# RemoteR1_0.net
KiCad netlist of a schematic drawn in EAGLE
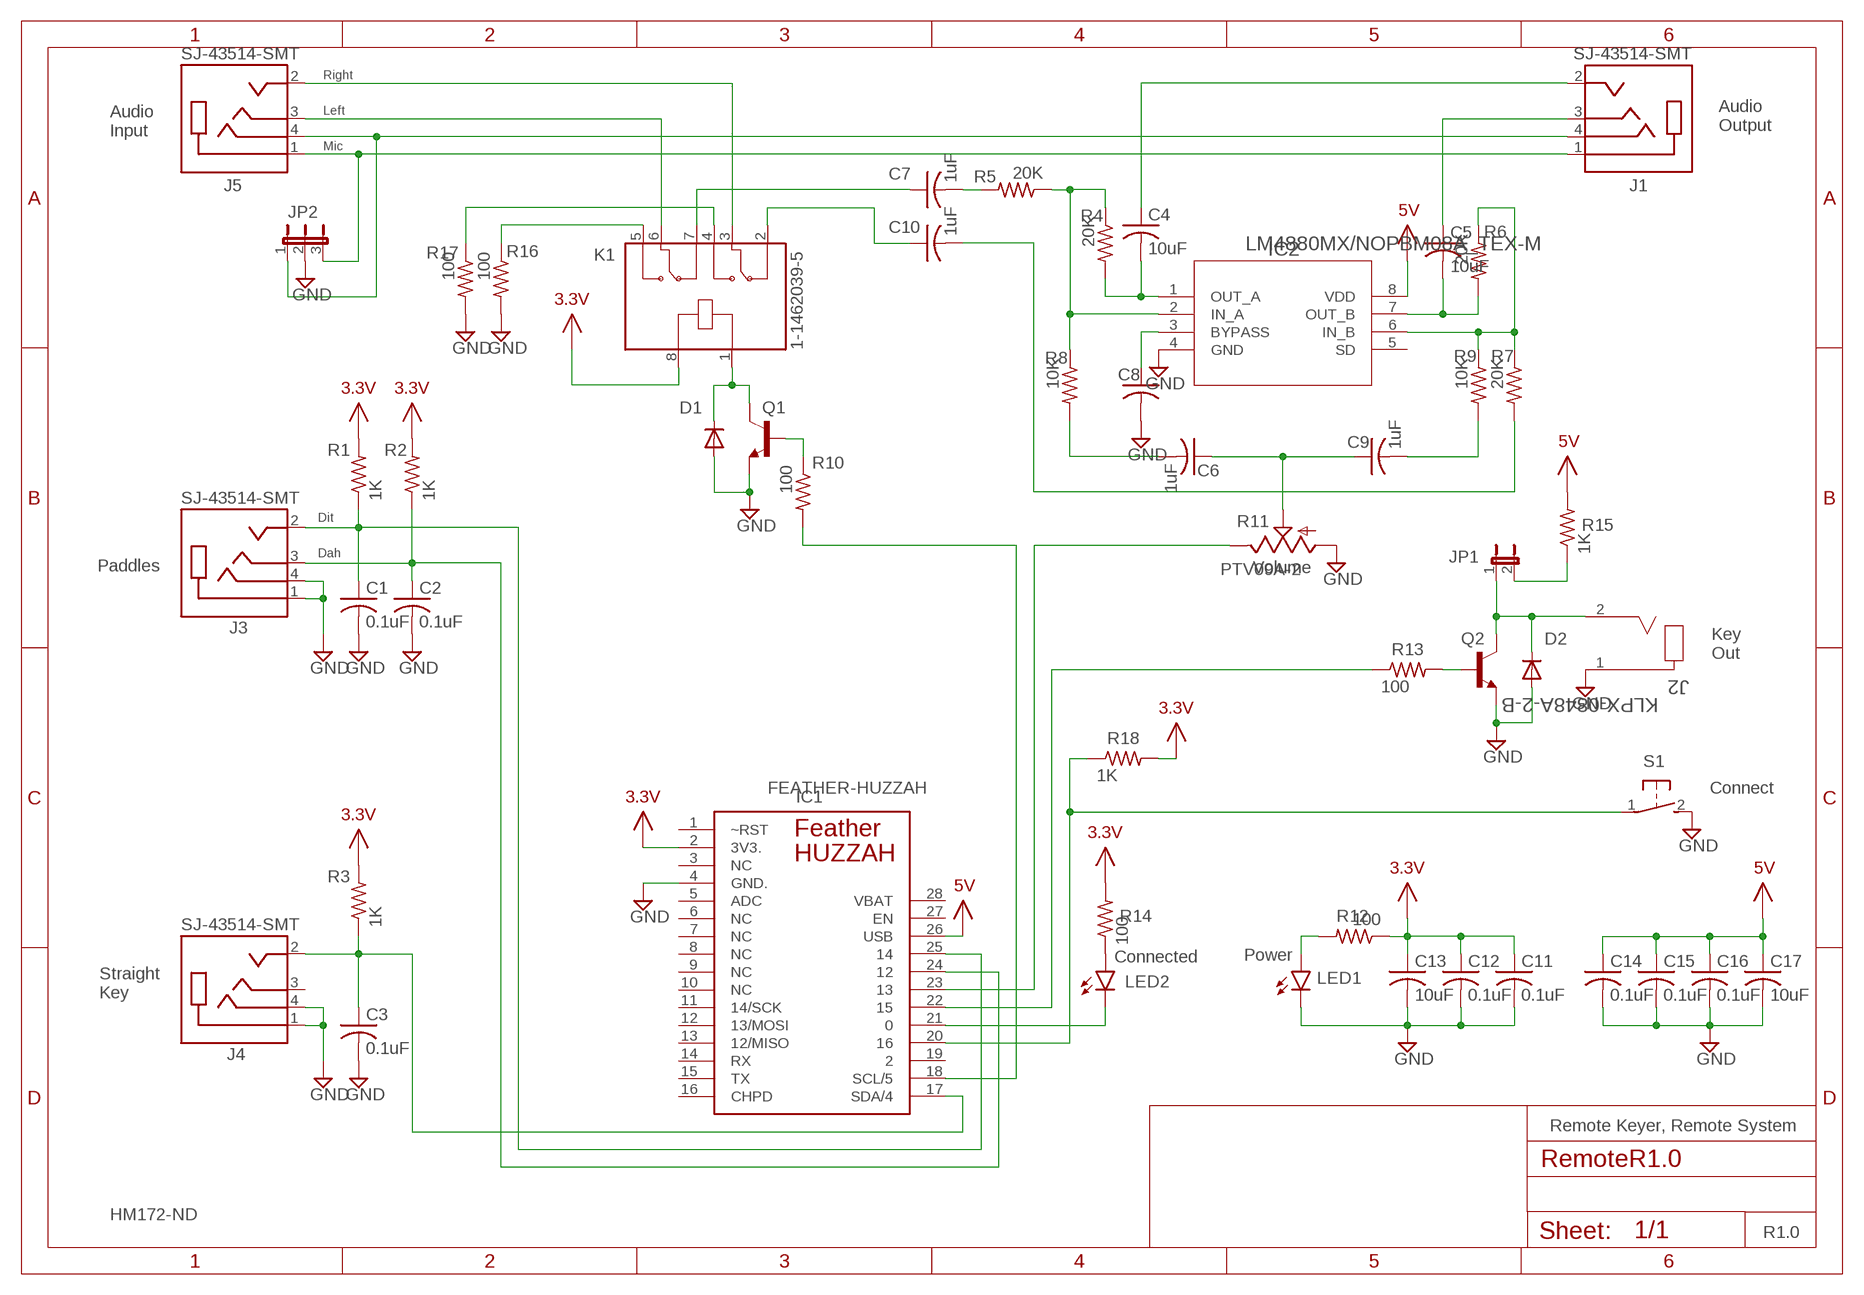
[diagram p0: schematic, sheet 1]

(export (version "E")
  (design (tool "Eeschema 10.0.6"))
  (components
    (comp (ref "C1")
      (value "0.1uF")
      (footprint "eagle-import:C0805")
      (libsource (lib "eagle-import") (part "C-USC0805"))
    )
    (comp (ref "C2")
      (value "0.1uF")
      (footprint "eagle-import:C0805")
      (libsource (lib "eagle-import") (part "C-USC0805"))
    )
    (comp (ref "C3")
      (value "0.1uF")
      (footprint "eagle-import:C0805")
      (libsource (lib "eagle-import") (part "C-USC0805"))
    )
    (comp (ref "C4")
      (value "10uF")
      (footprint "eagle-import:C1206")
      (libsource (lib "eagle-import") (part "C-USC1206"))
    )
    (comp (ref "C5")
      (value "10uF")
      (footprint "eagle-import:C1206")
      (libsource (lib "eagle-import") (part "C-USC1206"))
    )
    (comp (ref "C6")
      (value "1uF")
      (footprint "eagle-import:C0805")
      (libsource (lib "eagle-import") (part "C-USC0805"))
    )
    (comp (ref "C7")
      (value "1uF")
      (footprint "eagle-import:C0805")
      (libsource (lib "eagle-import") (part "C-USC0805"))
    )
    (comp (ref "C8")
      (value "C-USC0805")
      (footprint "eagle-import:C0805")
      (libsource (lib "eagle-import") (part "C-USC0805"))
    )
    (comp (ref "C9")
      (value "1uF")
      (footprint "eagle-import:C0805")
      (libsource (lib "eagle-import") (part "C-USC0805"))
    )
    (comp (ref "C10")
      (value "1uF")
      (footprint "eagle-import:C0805")
      (libsource (lib "eagle-import") (part "C-USC0805"))
    )
    (comp (ref "C11")
      (value "0.1uF")
      (footprint "eagle-import:C0805")
      (libsource (lib "eagle-import") (part "C-USC0805"))
    )
    (comp (ref "C12")
      (value "0.1uF")
      (footprint "eagle-import:C0805")
      (libsource (lib "eagle-import") (part "C-USC0805"))
    )
    (comp (ref "C13")
      (value "10uF")
      (footprint "eagle-import:C0805")
      (libsource (lib "eagle-import") (part "C-USC0805"))
    )
    (comp (ref "C14")
      (value "0.1uF")
      (footprint "eagle-import:C0805")
      (libsource (lib "eagle-import") (part "C-USC0805"))
    )
    (comp (ref "C15")
      (value "0.1uF")
      (footprint "eagle-import:C0805")
      (libsource (lib "eagle-import") (part "C-USC0805"))
    )
    (comp (ref "C16")
      (value "0.1uF")
      (footprint "eagle-import:C0805")
      (libsource (lib "eagle-import") (part "C-USC0805"))
    )
    (comp (ref "C17")
      (value "10uF")
      (footprint "eagle-import:C0805")
      (libsource (lib "eagle-import") (part "C-USC0805"))
    )
    (comp (ref "D1")
      (value "DIODE-SOD323-R")
      (footprint "eagle-import:SOD323-R")
      (libsource (lib "eagle-import") (part "DIODE-SOD323-R"))
    )
    (comp (ref "D2")
      (value "DIODE-SOD323-R")
      (footprint "eagle-import:SOD323-R")
      (libsource (lib "eagle-import") (part "DIODE-SOD323-R"))
    )
    (comp (ref "IC1")
      (value "FEATHER-HUZZAH")
      (footprint "eagle-import:FEATHER-HUZZAH")
      (libsource (lib "eagle-import") (part "FEATHER-HUZZAH"))
    )
    (comp (ref "IC2")
      (value "LM4880MX/NOPBM08A_TEX-M")
      (footprint "eagle-import:M08A_TEX-M")
      (fields
        (field (name "MANUFACTURER_PART_NUMBER") "LM4880MX/NOPB")
        (field (name "COPYRIGHT") "Copyright (C) 2021 Ultra Librarian. All rights reserved.")
      )
      (libsource (lib "eagle-import") (part "LM4880MX/NOPBM08A_TEX-M"))
    )
    (comp (ref "J1")
      (value "SJ-43514-SMT")
      (footprint "eagle-import:CUI_SJ-43514-SMT")
      (fields (field (name "MF") "CUI Devices") (field (name "MP") "SJ-43514-SMT-TR"))
      (libsource (lib "eagle-import") (part "SJ-43514-SMT"))
    )
    (comp (ref "J2")
      (value "KLPX-0848A-2-B")
      (footprint "eagle-import:KLPX-0848A-2-B_KYC")
      (fields (field (name "COPYRIGHT") "Copyright (C) 2021 Ultra Librarian. All rights reserved."))
      (libsource (lib "eagle-import") (part "KLPX-0848A-2-B"))
    )
    (comp (ref "J3")
      (value "SJ-43514-SMT")
      (footprint "eagle-import:CUI_SJ-43514-SMT")
      (fields (field (name "MF") "CUI Devices") (field (name "MP") "SJ-43514-SMT-TR"))
      (libsource (lib "eagle-import") (part "SJ-43514-SMT"))
    )
    (comp (ref "J4")
      (value "SJ-43514-SMT")
      (footprint "eagle-import:CUI_SJ-43514-SMT")
      (fields (field (name "MF") "CUI Devices") (field (name "MP") "SJ-43514-SMT-TR"))
      (libsource (lib "eagle-import") (part "SJ-43514-SMT"))
    )
    (comp (ref "J5")
      (value "SJ-43514-SMT")
      (footprint "eagle-import:CUI_SJ-43514-SMT")
      (fields (field (name "MF") "CUI Devices") (field (name "MP") "SJ-43514-SMT-TR"))
      (libsource (lib "eagle-import") (part "SJ-43514-SMT"))
    )
    (comp (ref "JP1")
      (value "JP1E")
      (footprint "eagle-import:JP1")
      (libsource (lib "eagle-import") (part "JP1E"))
    )
    (comp (ref "JP2")
      (value "JP2E")
      (footprint "eagle-import:JP2")
      (libsource (lib "eagle-import") (part "JP2E"))
    )
    (comp (ref "K1")
      (value "1-1462039-5")
      (footprint "eagle-import:RELAY_1-1462039-5")
      (fields (field (name "DIGI-KEY_PART_NUMBER") "PB1167-ND") (field (name "MF") "TE Connectivity"))
      (libsource (lib "eagle-import") (part "1-1462039-5"))
    )
    (comp (ref "LED1")
      (value "LED5MM")
      (footprint "eagle-import:LED5MM")
      (libsource (lib "eagle-import") (part "LED5MM"))
    )
    (comp (ref "LED2")
      (value "LED5MM")
      (footprint "eagle-import:LED5MM")
      (libsource (lib "eagle-import") (part "LED5MM"))
    )
    (comp (ref "Q1")
      (value "MMBT2369LT1-NPN-SOT23-BEC")
      (footprint "eagle-import:SOT23-BEC")
      (libsource (lib "eagle-import") (part "-NPN-SOT23-BECMMBT2369LT1"))
    )
    (comp (ref "Q2")
      (value "MMBT2369LT1-NPN-SOT23-BEC")
      (footprint "eagle-import:SOT23-BEC")
      (libsource (lib "eagle-import") (part "-NPN-SOT23-BECMMBT2369LT1"))
    )
    (comp (ref "R1")
      (value "1K")
      (footprint "eagle-import:R0805")
      (libsource (lib "eagle-import") (part "R-US_R0805"))
    )
    (comp (ref "R2")
      (value "1K")
      (footprint "eagle-import:R0805")
      (libsource (lib "eagle-import") (part "R-US_R0805"))
    )
    (comp (ref "R3")
      (value "1K")
      (footprint "eagle-import:R0805")
      (libsource (lib "eagle-import") (part "R-US_R0805"))
    )
    (comp (ref "R4")
      (value "20K")
      (footprint "eagle-import:R0805")
      (libsource (lib "eagle-import") (part "R-US_R0805"))
    )
    (comp (ref "R5")
      (value "20K")
      (footprint "eagle-import:R0805")
      (libsource (lib "eagle-import") (part "R-US_R0805"))
    )
    (comp (ref "R6")
      (value "20K")
      (footprint "eagle-import:R0805")
      (libsource (lib "eagle-import") (part "R-US_R0805"))
    )
    (comp (ref "R7")
      (value "20K")
      (footprint "eagle-import:R0805")
      (libsource (lib "eagle-import") (part "R-US_R0805"))
    )
    (comp (ref "R8")
      (value "10K")
      (footprint "eagle-import:R0805")
      (libsource (lib "eagle-import") (part "R-US_R0805"))
    )
    (comp (ref "R9")
      (value "10K")
      (footprint "eagle-import:R0805")
      (libsource (lib "eagle-import") (part "R-US_R0805"))
    )
    (comp (ref "R10")
      (value "100")
      (footprint "eagle-import:R0805")
      (libsource (lib "eagle-import") (part "R-US_R0805"))
    )
    (comp (ref "R11")
      (value "PTV09A-2")
      (footprint "eagle-import:PTV09A-2")
      (libsource (lib "eagle-import") (part "PTV09A-2"))
    )
    (comp (ref "R12")
      (value "100")
      (footprint "eagle-import:R0805")
      (libsource (lib "eagle-import") (part "R-US_R0805"))
    )
    (comp (ref "R13")
      (value "100")
      (footprint "eagle-import:R0805")
      (libsource (lib "eagle-import") (part "R-US_R0805"))
    )
    (comp (ref "R14")
      (value "100")
      (footprint "eagle-import:R0805")
      (libsource (lib "eagle-import") (part "R-US_R0805"))
    )
    (comp (ref "R15")
      (value "1K")
      (footprint "eagle-import:R0805")
      (libsource (lib "eagle-import") (part "R-US_R0805"))
    )
    (comp (ref "R16")
      (value "100")
      (footprint "eagle-import:R1206")
      (libsource (lib "eagle-import") (part "R-US_R1206"))
    )
    (comp (ref "R17")
      (value "100")
      (footprint "eagle-import:R1206")
      (libsource (lib "eagle-import") (part "R-US_R1206"))
    )
    (comp (ref "R18")
      (value "1K")
      (footprint "eagle-import:R0805")
      (libsource (lib "eagle-import") (part "R-US_R0805"))
    )
    (comp (ref "S1")
      (value "31-XX")
      (footprint "eagle-import:B3F-31XX")
      (fields (field (name "MPN") "B3F-3100"))
      (libsource (lib "eagle-import") (part "31-XX"))
    )
  )
  (nets
    (net (code "1") (name "/CHPD") (class "Default")
      (node (ref "IC1") (pin "16") (pinfunction "CHPD_16") (pintype "power_in"))
    )
    (net (code "2") (name "/VBAT") (class "Default")
      (node (ref "IC1") (pin "28") (pinfunction "VBAT_28") (pintype "power_in"))
    )
    (net (code "3") (name "3.3V") (class "Default")
      (node (ref "C11") (pin "1") (pinfunction "1_1") (pintype "passive"))
      (node (ref "C12") (pin "1") (pinfunction "1_1") (pintype "passive"))
      (node (ref "C13") (pin "1") (pinfunction "1_1") (pintype "passive"))
      (node (ref "IC1") (pin "2") (pinfunction "3V3._2") (pintype "power_in"))
      (node (ref "K1") (pin "8") (pinfunction "8_8") (pintype "passive"))
      (node (ref "R1") (pin "2") (pinfunction "2_2") (pintype "passive"))
      (node (ref "R12") (pin "1") (pinfunction "1_1") (pintype "passive"))
      (node (ref "R14") (pin "2") (pinfunction "2_2") (pintype "passive"))
      (node (ref "R18") (pin "2") (pinfunction "2_2") (pintype "passive"))
      (node (ref "R2") (pin "2") (pinfunction "2_2") (pintype "passive"))
      (node (ref "R3") (pin "2") (pinfunction "2_2") (pintype "passive"))
    )
    (net (code "4") (name "5V") (class "Default")
      (node (ref "C14") (pin "1") (pinfunction "1_1") (pintype "passive"))
      (node (ref "C15") (pin "1") (pinfunction "1_1") (pintype "passive"))
      (node (ref "C16") (pin "1") (pinfunction "1_1") (pintype "passive"))
      (node (ref "C17") (pin "1") (pinfunction "1_1") (pintype "passive"))
      (node (ref "IC1") (pin "26") (pinfunction "USB_26") (pintype "power_in"))
      (node (ref "IC2") (pin "8") (pinfunction "VDD_8") (pintype "power_in"))
      (node (ref "R15") (pin "2") (pinfunction "2_2") (pintype "passive"))
    )
    (net (code "5") (name "GND") (class "Default")
      (node (ref "C1") (pin "2") (pinfunction "2_2") (pintype "passive"))
      (node (ref "C11") (pin "2") (pinfunction "2_2") (pintype "passive"))
      (node (ref "C12") (pin "2") (pinfunction "2_2") (pintype "passive"))
      (node (ref "C13") (pin "2") (pinfunction "2_2") (pintype "passive"))
      (node (ref "C14") (pin "2") (pinfunction "2_2") (pintype "passive"))
      (node (ref "C15") (pin "2") (pinfunction "2_2") (pintype "passive"))
      (node (ref "C16") (pin "2") (pinfunction "2_2") (pintype "passive"))
      (node (ref "C17") (pin "2") (pinfunction "2_2") (pintype "passive"))
      (node (ref "C2") (pin "2") (pinfunction "2_2") (pintype "passive"))
      (node (ref "C3") (pin "2") (pinfunction "2_2") (pintype "passive"))
      (node (ref "C8") (pin "2") (pinfunction "2_2") (pintype "passive"))
      (node (ref "D1") (pin "A") (pinfunction "A_A") (pintype "passive"))
      (node (ref "D2") (pin "A") (pinfunction "A_A") (pintype "passive"))
      (node (ref "IC1") (pin "4") (pinfunction "GND._4") (pintype "power_in"))
      (node (ref "IC2") (pin "4") (pinfunction "GND_4") (pintype "power_in"))
      (node (ref "J2") (pin "1") (pinfunction "1_1") (pintype "passive"))
      (node (ref "J3") (pin "1") (pinfunction "SLEEVE_1") (pintype "passive"))
      (node (ref "J3") (pin "4") (pinfunction "RING2_4") (pintype "passive"))
      (node (ref "J4") (pin "1") (pinfunction "SLEEVE_1") (pintype "passive"))
      (node (ref "J4") (pin "4") (pinfunction "RING2_4") (pintype "passive"))
      (node (ref "JP2") (pin "2") (pinfunction "2_2") (pintype "passive"))
      (node (ref "LED1") (pin "K") (pinfunction "C_K") (pintype "passive"))
      (node (ref "Q1") (pin "E") (pinfunction "E_E") (pintype "passive"))
      (node (ref "Q2") (pin "E") (pinfunction "E_E") (pintype "passive"))
      (node (ref "R11") (pin "1") (pinfunction "A_1") (pintype "passive"))
      (node (ref "R16") (pin "2") (pinfunction "2_2") (pintype "passive"))
      (node (ref "R17") (pin "2") (pinfunction "2_2") (pintype "passive"))
      (node (ref "S1") (pin "2") (pinfunction "S_2") (pintype "passive"))
    )
    (net (code "6") (name "Net-(C6-Pad2)") (class "Default")
      (node (ref "C6") (pin "2") (pinfunction "2_2") (pintype "passive"))
      (node (ref "R8") (pin "2") (pinfunction "2_2") (pintype "passive"))
    )
    (net (code "7") (name "Net-(C7-Pad1)") (class "Default")
      (node (ref "C7") (pin "1") (pinfunction "1_1") (pintype "passive"))
      (node (ref "K1") (pin "7") (pinfunction "7_7") (pintype "passive"))
    )
    (net (code "8") (name "Net-(C7-Pad2)") (class "Default")
      (node (ref "C7") (pin "2") (pinfunction "2_2") (pintype "passive"))
      (node (ref "R5") (pin "2") (pinfunction "2_2") (pintype "passive"))
    )
    (net (code "9") (name "Net-(C9-Pad2)") (class "Default")
      (node (ref "C9") (pin "2") (pinfunction "2_2") (pintype "passive"))
      (node (ref "R9") (pin "2") (pinfunction "2_2") (pintype "passive"))
    )
    (net (code "10") (name "Net-(C10-Pad1)") (class "Default")
      (node (ref "C10") (pin "1") (pinfunction "1_1") (pintype "passive"))
      (node (ref "K1") (pin "2") (pinfunction "2_2") (pintype "passive"))
    )
    (net (code "11") (name "Net-(C10-Pad2)") (class "Default")
      (node (ref "C10") (pin "2") (pinfunction "2_2") (pintype "passive"))
      (node (ref "R7") (pin "2") (pinfunction "2_2") (pintype "passive"))
    )
    (net (code "12") (name "Net-(D1-PadC)") (class "Default")
      (node (ref "D1") (pin "C") (pinfunction "C_C") (pintype "passive"))
      (node (ref "K1") (pin "1") (pinfunction "1_1") (pintype "passive"))
      (node (ref "Q1") (pin "C") (pinfunction "C_C") (pintype "passive"))
    )
    (net (code "13") (name "Net-(D2-PadC)") (class "Default")
      (node (ref "D2") (pin "C") (pinfunction "C_C") (pintype "passive"))
      (node (ref "J2") (pin "2") (pinfunction "2_2") (pintype "passive"))
      (node (ref "JP1") (pin "1") (pinfunction "1_1") (pintype "passive"))
      (node (ref "Q2") (pin "C") (pinfunction "C_C") (pintype "passive"))
    )
    (net (code "14") (name "Net-(IC1-0)") (class "Default")
      (node (ref "IC1") (pin "21") (pinfunction "0_21") (pintype "bidirectional"))
      (node (ref "LED2") (pin "K") (pinfunction "C_K") (pintype "passive"))
    )
    (net (code "15") (name "Net-(IC1-12)") (class "Default")
      (node (ref "C2") (pin "1") (pinfunction "1_1") (pintype "passive"))
      (node (ref "IC1") (pin "24") (pinfunction "12_24") (pintype "bidirectional"))
      (node (ref "J3") (pin "3") (pinfunction "RING1_3") (pintype "passive"))
      (node (ref "R2") (pin "1") (pinfunction "1_1") (pintype "passive"))
    )
    (net (code "16") (name "Net-(IC1-13)") (class "Default")
      (node (ref "IC1") (pin "23") (pinfunction "13_23") (pintype "bidirectional"))
      (node (ref "R11") (pin "3") (pinfunction "E_3") (pintype "passive"))
    )
    (net (code "17") (name "Net-(IC1-14)") (class "Default")
      (node (ref "C1") (pin "1") (pinfunction "1_1") (pintype "passive"))
      (node (ref "IC1") (pin "25") (pinfunction "14_25") (pintype "bidirectional"))
      (node (ref "J3") (pin "2") (pinfunction "TIP_2") (pintype "passive"))
      (node (ref "R1") (pin "1") (pinfunction "1_1") (pintype "passive"))
    )
    (net (code "18") (name "Net-(IC1-15)") (class "Default")
      (node (ref "IC1") (pin "22") (pinfunction "15_22") (pintype "bidirectional"))
      (node (ref "R13") (pin "1") (pinfunction "1_1") (pintype "passive"))
    )
    (net (code "19") (name "Net-(IC1-16)") (class "Default")
      (node (ref "IC1") (pin "20") (pinfunction "16_20") (pintype "bidirectional"))
      (node (ref "R18") (pin "1") (pinfunction "1_1") (pintype "passive"))
      (node (ref "S1") (pin "1") (pinfunction "P_1") (pintype "passive"))
    )
    (net (code "20") (name "Net-(IC1-SCL{slash}5)") (class "Default")
      (node (ref "IC1") (pin "18") (pinfunction "SCL/5_18") (pintype "bidirectional"))
      (node (ref "R10") (pin "2") (pinfunction "2_2") (pintype "passive"))
    )
    (net (code "21") (name "Net-(IC1-SDA{slash}4)") (class "Default")
      (node (ref "C3") (pin "1") (pinfunction "1_1") (pintype "passive"))
      (node (ref "IC1") (pin "17") (pinfunction "SDA/4_17") (pintype "bidirectional"))
      (node (ref "J4") (pin "2") (pinfunction "TIP_2") (pintype "passive"))
      (node (ref "R3") (pin "1") (pinfunction "1_1") (pintype "passive"))
    )
    (net (code "22") (name "Net-(IC2-BYPASS)") (class "Default")
      (node (ref "C8") (pin "1") (pinfunction "1_1") (pintype "passive"))
      (node (ref "IC2") (pin "3") (pinfunction "BYPASS_3") (pintype "passive"))
    )
    (net (code "23") (name "Net-(IC2-IN_A)") (class "Default")
      (node (ref "IC2") (pin "2") (pinfunction "IN_A_2") (pintype "input"))
      (node (ref "R4") (pin "1") (pinfunction "1_1") (pintype "passive"))
      (node (ref "R5") (pin "1") (pinfunction "1_1") (pintype "passive"))
      (node (ref "R8") (pin "1") (pinfunction "1_1") (pintype "passive"))
    )
    (net (code "24") (name "Net-(IC2-IN_B)") (class "Default")
      (node (ref "IC2") (pin "6") (pinfunction "IN_B_6") (pintype "input"))
      (node (ref "R6") (pin "1") (pinfunction "1_1") (pintype "passive"))
      (node (ref "R7") (pin "1") (pinfunction "1_1") (pintype "passive"))
      (node (ref "R9") (pin "1") (pinfunction "1_1") (pintype "passive"))
    )
    (net (code "25") (name "Net-(IC2-OUT_A)") (class "Default")
      (node (ref "C4") (pin "2") (pinfunction "2_2") (pintype "passive"))
      (node (ref "IC2") (pin "1") (pinfunction "OUT_A_1") (pintype "output"))
      (node (ref "R4") (pin "2") (pinfunction "2_2") (pintype "passive"))
    )
    (net (code "26") (name "Net-(IC2-OUT_B)") (class "Default")
      (node (ref "C5") (pin "2") (pinfunction "2_2") (pintype "passive"))
      (node (ref "IC2") (pin "7") (pinfunction "OUT_B_7") (pintype "output"))
      (node (ref "R6") (pin "2") (pinfunction "2_2") (pintype "passive"))
    )
    (net (code "27") (name "Net-(J1-RING1)") (class "Default")
      (node (ref "C5") (pin "1") (pinfunction "1_1") (pintype "passive"))
      (node (ref "J1") (pin "3") (pinfunction "RING1_3") (pintype "passive"))
    )
    (net (code "28") (name "Net-(J1-RING2)") (class "Default")
      (node (ref "J1") (pin "4") (pinfunction "RING2_4") (pintype "passive"))
      (node (ref "J5") (pin "4") (pinfunction "RING2_4") (pintype "passive"))
      (node (ref "JP2") (pin "1") (pinfunction "1_1") (pintype "passive"))
    )
    (net (code "29") (name "Net-(J1-SLEEVE)") (class "Default")
      (node (ref "J1") (pin "1") (pinfunction "SLEEVE_1") (pintype "passive"))
      (node (ref "J5") (pin "1") (pinfunction "SLEEVE_1") (pintype "passive"))
      (node (ref "JP2") (pin "3") (pinfunction "3_3") (pintype "passive"))
    )
    (net (code "30") (name "Net-(J1-TIP)") (class "Default")
      (node (ref "C4") (pin "1") (pinfunction "1_1") (pintype "passive"))
      (node (ref "J1") (pin "2") (pinfunction "TIP_2") (pintype "passive"))
    )
    (net (code "31") (name "Net-(J5-RING1)") (class "Default")
      (node (ref "J5") (pin "3") (pinfunction "RING1_3") (pintype "passive"))
      (node (ref "K1") (pin "6") (pinfunction "6_6") (pintype "passive"))
    )
    (net (code "32") (name "Net-(J5-TIP)") (class "Default")
      (node (ref "J5") (pin "2") (pinfunction "TIP_2") (pintype "passive"))
      (node (ref "K1") (pin "3") (pinfunction "3_3") (pintype "passive"))
    )
    (net (code "33") (name "Net-(JP1-Pad2)") (class "Default")
      (node (ref "JP1") (pin "2") (pinfunction "2_2") (pintype "passive"))
      (node (ref "R15") (pin "1") (pinfunction "1_1") (pintype "passive"))
    )
    (net (code "34") (name "Net-(K1-Pad4)") (class "Default")
      (node (ref "K1") (pin "4") (pinfunction "4_4") (pintype "passive"))
      (node (ref "R17") (pin "1") (pinfunction "1_1") (pintype "passive"))
    )
    (net (code "35") (name "Net-(K1-Pad5)") (class "Default")
      (node (ref "K1") (pin "5") (pinfunction "5_5") (pintype "passive"))
      (node (ref "R16") (pin "1") (pinfunction "1_1") (pintype "passive"))
    )
    (net (code "36") (name "Net-(LED1-PadA)") (class "Default")
      (node (ref "LED1") (pin "A") (pinfunction "A_A") (pintype "passive"))
      (node (ref "R12") (pin "2") (pinfunction "2_2") (pintype "passive"))
    )
    (net (code "37") (name "Net-(LED2-PadA)") (class "Default")
      (node (ref "LED2") (pin "A") (pinfunction "A_A") (pintype "passive"))
      (node (ref "R14") (pin "1") (pinfunction "1_1") (pintype "passive"))
    )
    (net (code "38") (name "Net-(Q1-PadB)") (class "Default")
      (node (ref "Q1") (pin "B") (pinfunction "B_B") (pintype "passive"))
      (node (ref "R10") (pin "1") (pinfunction "1_1") (pintype "passive"))
    )
    (net (code "39") (name "Net-(Q2-PadB)") (class "Default")
      (node (ref "Q2") (pin "B") (pinfunction "B_B") (pintype "passive"))
      (node (ref "R13") (pin "2") (pinfunction "2_2") (pintype "passive"))
    )
    (net (code "40") (name "Net-(R11-S)") (class "Default")
      (node (ref "C6") (pin "1") (pinfunction "1_1") (pintype "passive"))
      (node (ref "C9") (pin "1") (pinfunction "1_1") (pintype "passive"))
      (node (ref "R11") (pin "2") (pinfunction "S_2") (pintype "passive"))
    )
    (net (code "41") (name "unconnected-(IC1-2-Pad19)") (class "Default")
      (node (ref "IC1") (pin "19") (pinfunction "2_19") (pintype "bidirectional"))
    )
    (net (code "42") (name "unconnected-(IC1-12{slash}MISO-Pad13)") (class "Default")
      (node (ref "IC1") (pin "13") (pinfunction "12/MISO_13") (pintype "bidirectional"))
    )
    (net (code "43") (name "unconnected-(IC1-13{slash}MOSI-Pad12)") (class "Default")
      (node (ref "IC1") (pin "12") (pinfunction "13/MOSI_12") (pintype "bidirectional"))
    )
    (net (code "44") (name "unconnected-(IC1-14{slash}SCK-Pad11)") (class "Default")
      (node (ref "IC1") (pin "11") (pinfunction "14/SCK_11") (pintype "bidirectional"))
    )
    (net (code "45") (name "unconnected-(IC1-ADC-Pad5)") (class "Default")
      (node (ref "IC1") (pin "5") (pinfunction "ADC_5") (pintype "bidirectional"))
    )
    (net (code "46") (name "unconnected-(IC1-EN-Pad27)") (class "Default")
      (node (ref "IC1") (pin "27") (pinfunction "EN_27") (pintype "input"))
    )
    (net (code "47") (name "unconnected-(IC1-NC-Pad3)") (class "Default")
      (node (ref "IC1") (pin "3") (pinfunction "NC_3") (pintype "input"))
    )
    (net (code "48") (name "unconnected-(IC1-NC-Pad6)") (class "Default")
      (node (ref "IC1") (pin "6") (pinfunction "NC_6") (pintype "bidirectional"))
    )
    (net (code "49") (name "unconnected-(IC1-NC-Pad7)") (class "Default")
      (node (ref "IC1") (pin "7") (pinfunction "NC_7") (pintype "bidirectional"))
    )
    (net (code "50") (name "unconnected-(IC1-NC-Pad8)") (class "Default")
      (node (ref "IC1") (pin "8") (pinfunction "NC_8") (pintype "bidirectional"))
    )
    (net (code "51") (name "unconnected-(IC1-NC-Pad9)") (class "Default")
      (node (ref "IC1") (pin "9") (pinfunction "NC_9") (pintype "bidirectional"))
    )
    (net (code "52") (name "unconnected-(IC1-NC-Pad10)") (class "Default")
      (node (ref "IC1") (pin "10") (pinfunction "NC_10") (pintype "bidirectional"))
    )
    (net (code "53") (name "unconnected-(IC1-RX-Pad14)") (class "Default")
      (node (ref "IC1") (pin "14") (pinfunction "RX_14") (pintype "bidirectional"))
    )
    (net (code "54") (name "unconnected-(IC1-TX-Pad15)") (class "Default")
      (node (ref "IC1") (pin "15") (pinfunction "TX_15") (pintype "bidirectional"))
    )
    (net (code "55") (name "unconnected-(IC1-~{RST}-Pad1)") (class "Default")
      (node (ref "IC1") (pin "1") (pinfunction "~{RST}_1") (pintype "input"))
    )
    (net (code "56") (name "unconnected-(IC2-SD-Pad5)") (class "Default")
      (node (ref "IC2") (pin "5") (pinfunction "SD_5") (pintype "input"))
    )
    (net (code "57") (name "unconnected-(J4-RING1-Pad3)") (class "Default")
      (node (ref "J4") (pin "3") (pinfunction "RING1_3") (pintype "passive"))
    )
  )
)
